# Game_Consol_Power.net
KiCad netlist of a schematic drawn in Altium Designer
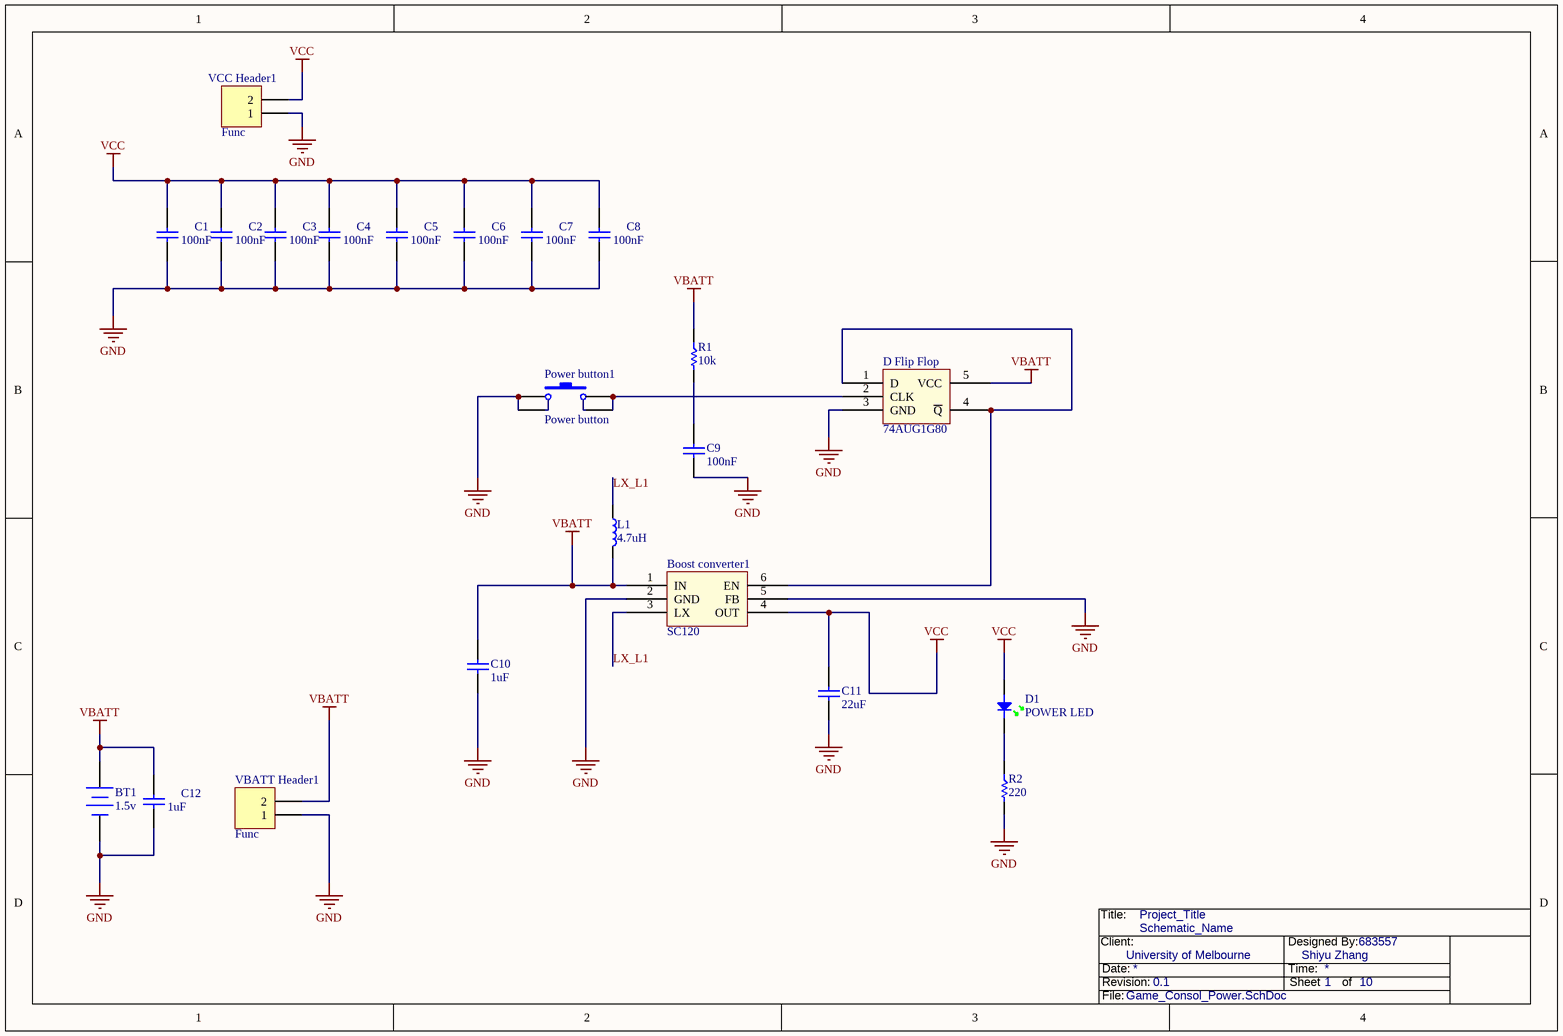
[diagram p0: Game_Consol_Power.SchDoc]

(export (version "E")
  (design (tool "Eeschema 10.0.6"))
  (components
    (comp (ref "Boost converter1")
      (value "SC120")
      (footprint "SOT23-6")
      (description "Regulator Low Voltage")
      (libsource (lib "EmbSD Lib 0v1") (part "SC120"))
    )
    (comp (ref "BT1")
      (value "1.5v")
      (footprint "BATT_HOLDER")
      (description "Battery Holder AA 1.5v")
      (fields (field (name "PUBLISHER") "Altium Limited"))
      (libsource (lib "EmbSD Lib 0v1") (part "BAT"))
    )
    (comp (ref "C1")
      (value "100nF")
      (footprint "0805")
      (description "Capacitor 100nF")
      (libsource (lib "EmbSD Lib 0v1") (part "C 0805"))
    )
    (comp (ref "C2")
      (value "100nF")
      (footprint "0805")
      (description "Capacitor 100nF")
      (libsource (lib "EmbSD Lib 0v1") (part "C 0805"))
    )
    (comp (ref "C3")
      (value "100nF")
      (footprint "0805")
      (description "Capacitor 100nF")
      (libsource (lib "EmbSD Lib 0v1") (part "C 0805"))
    )
    (comp (ref "C4")
      (value "100nF")
      (footprint "0805")
      (description "Capacitor 100nF")
      (libsource (lib "EmbSD Lib 0v1") (part "C 0805"))
    )
    (comp (ref "C5")
      (value "100nF")
      (footprint "0805")
      (description "Capacitor 100nF")
      (libsource (lib "EmbSD Lib 0v1") (part "C 0805"))
    )
    (comp (ref "C6")
      (value "100nF")
      (footprint "0805")
      (description "Capacitor 100nF")
      (libsource (lib "EmbSD Lib 0v1") (part "C 0805"))
    )
    (comp (ref "C7")
      (value "100nF")
      (footprint "0805")
      (description "Capacitor 100nF")
      (libsource (lib "EmbSD Lib 0v1") (part "C 0805"))
    )
    (comp (ref "C8")
      (value "100nF")
      (footprint "0805")
      (description "Capacitor 100nF")
      (libsource (lib "EmbSD Lib 0v1") (part "C 0805"))
    )
    (comp (ref "C9")
      (value "100nF")
      (footprint "0805")
      (description "Capacitor 100nF")
      (libsource (lib "EmbSD Lib 0v1") (part "C 0805"))
    )
    (comp (ref "C10")
      (value "1uF")
      (footprint "0805")
      (description "Capacitor 100nF")
      (libsource (lib "EmbSD Lib 0v1") (part "C 0805"))
    )
    (comp (ref "C11")
      (value "22uF")
      (footprint "1210")
      (description "Capacitor 22uF")
      (fields
        (field (name "MANUFACTURER") "Generic Components")
        (field (name "MANUFACTURER PART NUMBER") "LMK316F226ZL-T")
        (field (name "PUBLISHER") "Altium Limited")
      )
      (libsource (lib "EmbSD Lib 0v1") (part "C 1210"))
    )
    (comp (ref "C12")
      (value "1uF")
      (footprint "0805")
      (description "Capacitor 100nF")
      (libsource (lib "EmbSD Lib 0v1") (part "C 0805"))
    )
    (comp (ref "D Flip Flop")
      (value "74AUG1G80")
      (footprint "SOT23-5")
      (description "Inverted single D flip flop")
      (libsource (lib "EmbSD Lib 0v1") (part "74AUG1G80"))
    )
    (comp (ref "D1")
      (value "POWER LED")
      (footprint "0805D")
      (description "Light Emitting Diode")
      (fields (field (name "MANUFACTURER") "Generic Components") (field (name "PUBLISHER") "Altium Limited"))
      (libsource (lib "EmbSD Lib 0v1") (part "LED GREEN"))
    )
    (comp (ref "L1")
      (value "4.7uH")
      (footprint "1210L")
      (description "Inductor 4.7uH")
      (fields
        (field (name "MANUFACTURER") "Murata Electronics North America")
        (field (name "MANUFACTURER PART NUMBER") "LQH32CN4R7M23L")
        (field (name "PUBLISHER") "Altium Limited")
      )
      (libsource (lib "EmbSD Lib 0v1") (part "I 1210"))
    )
    (comp (ref "Power button1")
      (value "Power button")
      (footprint "SPNO_SMD")
      (description "Push Button Switch")
      (fields
        (field (name "MANUFACTURER") "TE Connectivity")
        (field (name "MANUFACTURER PART NUMBER") "FSM4JSMA")
        (field (name "PUBLISHER") "Altium Limited")
      )
      (libsource (lib "EmbSD Lib 0v1") (part "SW-PB"))
    )
    (comp (ref "R1")
      (value "10k")
      (footprint "0805")
      (description "Resistor")
      (libsource (lib "EmbSD Lib 0v1") (part "R"))
    )
    (comp (ref "R2")
      (value "220")
      (footprint "0805")
      (description "Resistor")
      (libsource (lib "EmbSD Lib 0v1") (part "R"))
    )
    (comp (ref "VBATT Header1")
      (value "Func")
      (footprint "HDR1X2")
      (description "2 Pin Header")
      (fields (field (name "PUBLISHER") "Altium Limited"))
      (libsource (lib "EmbSD Lib 0v1") (part "HDR2"))
    )
    (comp (ref "VCC Header1")
      (value "Func")
      (footprint "HDR1X2")
      (description "2 Pin Header")
      (fields (field (name "PUBLISHER") "Altium Limited"))
      (libsource (lib "EmbSD Lib 0v1") (part "HDR2"))
    )
  )
  (nets
    (net (code "1") (name "/LX_L1") (class "Default")
      (node (ref "Boost converter1") (pin "3") (pinfunction "LX_3") (pintype "passive"))
      (node (ref "L1") (pin "1") (pinfunction "1_1") (pintype "passive"))
    )
    (net (code "2") (name "GND") (class "Default")
      (node (ref "BT1") (pin "2") (pinfunction "-_2") (pintype "passive"))
      (node (ref "Boost converter1") (pin "2") (pinfunction "GND_2") (pintype "passive"))
      (node (ref "Boost converter1") (pin "5") (pinfunction "FB_5") (pintype "passive"))
      (node (ref "C1") (pin "2") (pinfunction "2_2") (pintype "passive"))
      (node (ref "C10") (pin "2") (pinfunction "2_2") (pintype "passive"))
      (node (ref "C11") (pin "2") (pinfunction "2_2") (pintype "passive"))
      (node (ref "C12") (pin "2") (pinfunction "2_2") (pintype "passive"))
      (node (ref "C2") (pin "2") (pinfunction "2_2") (pintype "passive"))
      (node (ref "C3") (pin "2") (pinfunction "2_2") (pintype "passive"))
      (node (ref "C4") (pin "2") (pinfunction "2_2") (pintype "passive"))
      (node (ref "C5") (pin "2") (pinfunction "2_2") (pintype "passive"))
      (node (ref "C6") (pin "2") (pinfunction "2_2") (pintype "passive"))
      (node (ref "C7") (pin "2") (pinfunction "2_2") (pintype "passive"))
      (node (ref "C8") (pin "2") (pinfunction "2_2") (pintype "passive"))
      (node (ref "C9") (pin "2") (pinfunction "2_2") (pintype "passive"))
      (node (ref "D Flip Flop") (pin "3") (pinfunction "GND_3") (pintype "passive"))
      (node (ref "Power button1") (pin "1") (pinfunction "1_1") (pintype "passive"))
      (node (ref "Power button1") (pin "2") (pinfunction "2_2") (pintype "passive"))
      (node (ref "R2") (pin "2") (pintype "passive"))
      (node (ref "VBATT Header1") (pin "1") (pinfunction "1_1") (pintype "passive"))
      (node (ref "VCC Header1") (pin "1") (pinfunction "1_1") (pintype "passive"))
    )
    (net (code "3") (name "Net-(Boost converter1-EN)") (class "Default")
      (node (ref "Boost converter1") (pin "6") (pinfunction "EN_6") (pintype "passive"))
      (node (ref "D Flip Flop") (pin "1") (pinfunction "D_1") (pintype "passive"))
      (node (ref "D Flip Flop") (pin "4") (pinfunction "~{Q}_4") (pintype "passive"))
    )
    (net (code "4") (name "Net-(C9-Pad1)") (class "Default")
      (node (ref "C9") (pin "1") (pinfunction "1_1") (pintype "passive"))
      (node (ref "R1") (pin "2") (pintype "passive"))
    )
    (net (code "5") (name "Net-(D Flip Flop-CLK)") (class "Default")
      (node (ref "D Flip Flop") (pin "2") (pinfunction "CLK_2") (pintype "passive"))
      (node (ref "Power button1") (pin "3") (pinfunction "3_3") (pintype "passive"))
      (node (ref "Power button1") (pin "4") (pinfunction "4_4") (pintype "passive"))
    )
    (net (code "6") (name "Net-(D1-PadK)") (class "Default")
      (node (ref "D1") (pin "K") (pinfunction "K_K") (pintype "passive"))
      (node (ref "R2") (pin "1") (pintype "passive"))
    )
    (net (code "7") (name "VBATT") (class "Default")
      (node (ref "BT1") (pin "1") (pinfunction "+_1") (pintype "passive"))
      (node (ref "Boost converter1") (pin "1") (pinfunction "IN_1") (pintype "passive"))
      (node (ref "C10") (pin "1") (pinfunction "1_1") (pintype "passive"))
      (node (ref "C12") (pin "1") (pinfunction "1_1") (pintype "passive"))
      (node (ref "D Flip Flop") (pin "5") (pinfunction "VCC_5") (pintype "passive"))
      (node (ref "L1") (pin "2") (pinfunction "2_2") (pintype "passive"))
      (node (ref "R1") (pin "1") (pintype "passive"))
      (node (ref "VBATT Header1") (pin "2") (pinfunction "2_2") (pintype "passive"))
    )
    (net (code "8") (name "VCC") (class "Default")
      (node (ref "Boost converter1") (pin "4") (pinfunction "OUT_4") (pintype "passive"))
      (node (ref "C1") (pin "1") (pinfunction "1_1") (pintype "passive"))
      (node (ref "C11") (pin "1") (pinfunction "1_1") (pintype "passive"))
      (node (ref "C2") (pin "1") (pinfunction "1_1") (pintype "passive"))
      (node (ref "C3") (pin "1") (pinfunction "1_1") (pintype "passive"))
      (node (ref "C4") (pin "1") (pinfunction "1_1") (pintype "passive"))
      (node (ref "C5") (pin "1") (pinfunction "1_1") (pintype "passive"))
      (node (ref "C6") (pin "1") (pinfunction "1_1") (pintype "passive"))
      (node (ref "C7") (pin "1") (pinfunction "1_1") (pintype "passive"))
      (node (ref "C8") (pin "1") (pinfunction "1_1") (pintype "passive"))
      (node (ref "D1") (pin "A") (pinfunction "A_A") (pintype "passive"))
      (node (ref "VCC Header1") (pin "2") (pinfunction "2_2") (pintype "passive"))
    )
  )
)
